# ts.net
KiCad netlist of a schematic drawn in EAGLE
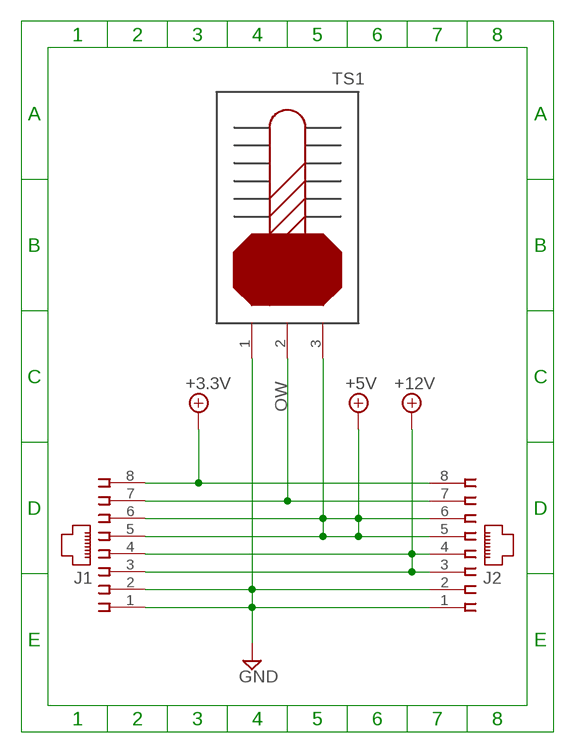
[diagram p0: schematic, sheet 1]

(export (version "E")
  (design (tool "Eeschema 10.0.6"))
  (components
    (comp (ref "J1")
      (value "215877-4")
      (footprint "eagle-import:215877-4")
      (libsource (lib "eagle-import") (part "215877-4"))
    )
    (comp (ref "J2")
      (value "215877-4")
      (footprint "eagle-import:215877-4")
      (libsource (lib "eagle-import") (part "215877-4"))
    )
    (comp (ref "TS1")
      (value "DS18B20")
      (footprint "eagle-import:KK-156-3")
      (libsource (lib "eagle-import") (part "DS18B20"))
    )
  )
  (nets
    (net (code "1") (name "+3.3V") (class "Default")
      (node (ref "J1") (pin "8") (pinfunction "8_8") (pintype "passive"))
      (node (ref "J2") (pin "8") (pinfunction "8_8") (pintype "passive"))
    )
    (net (code "2") (name "+5V") (class "Default")
      (node (ref "J1") (pin "5") (pinfunction "5_5") (pintype "passive"))
      (node (ref "J1") (pin "6") (pinfunction "6_6") (pintype "passive"))
      (node (ref "J2") (pin "5") (pinfunction "5_5") (pintype "passive"))
      (node (ref "J2") (pin "6") (pinfunction "6_6") (pintype "passive"))
      (node (ref "TS1") (pin "3") (pinfunction "P$3_3") (pintype "bidirectional"))
    )
    (net (code "3") (name "+12V") (class "Default")
      (node (ref "J1") (pin "3") (pinfunction "3_3") (pintype "passive"))
      (node (ref "J1") (pin "4") (pinfunction "4_4") (pintype "passive"))
      (node (ref "J2") (pin "3") (pinfunction "3_3") (pintype "passive"))
      (node (ref "J2") (pin "4") (pinfunction "4_4") (pintype "passive"))
    )
    (net (code "4") (name "/OW") (class "Default")
      (node (ref "J1") (pin "7") (pinfunction "7_7") (pintype "passive"))
      (node (ref "J2") (pin "7") (pinfunction "7_7") (pintype "passive"))
      (node (ref "TS1") (pin "2") (pinfunction "P$2_2") (pintype "bidirectional"))
    )
    (net (code "5") (name "GND") (class "Default")
      (node (ref "J1") (pin "1") (pinfunction "1_1") (pintype "passive"))
      (node (ref "J1") (pin "2") (pinfunction "2_2") (pintype "passive"))
      (node (ref "J2") (pin "1") (pinfunction "1_1") (pintype "passive"))
      (node (ref "J2") (pin "2") (pinfunction "2_2") (pintype "passive"))
      (node (ref "TS1") (pin "1") (pinfunction "P$1_1") (pintype "bidirectional"))
    )
  )
)
